# vidc_interposer2-PTH.net
KiCad netlist of a schematic drawn in EAGLE
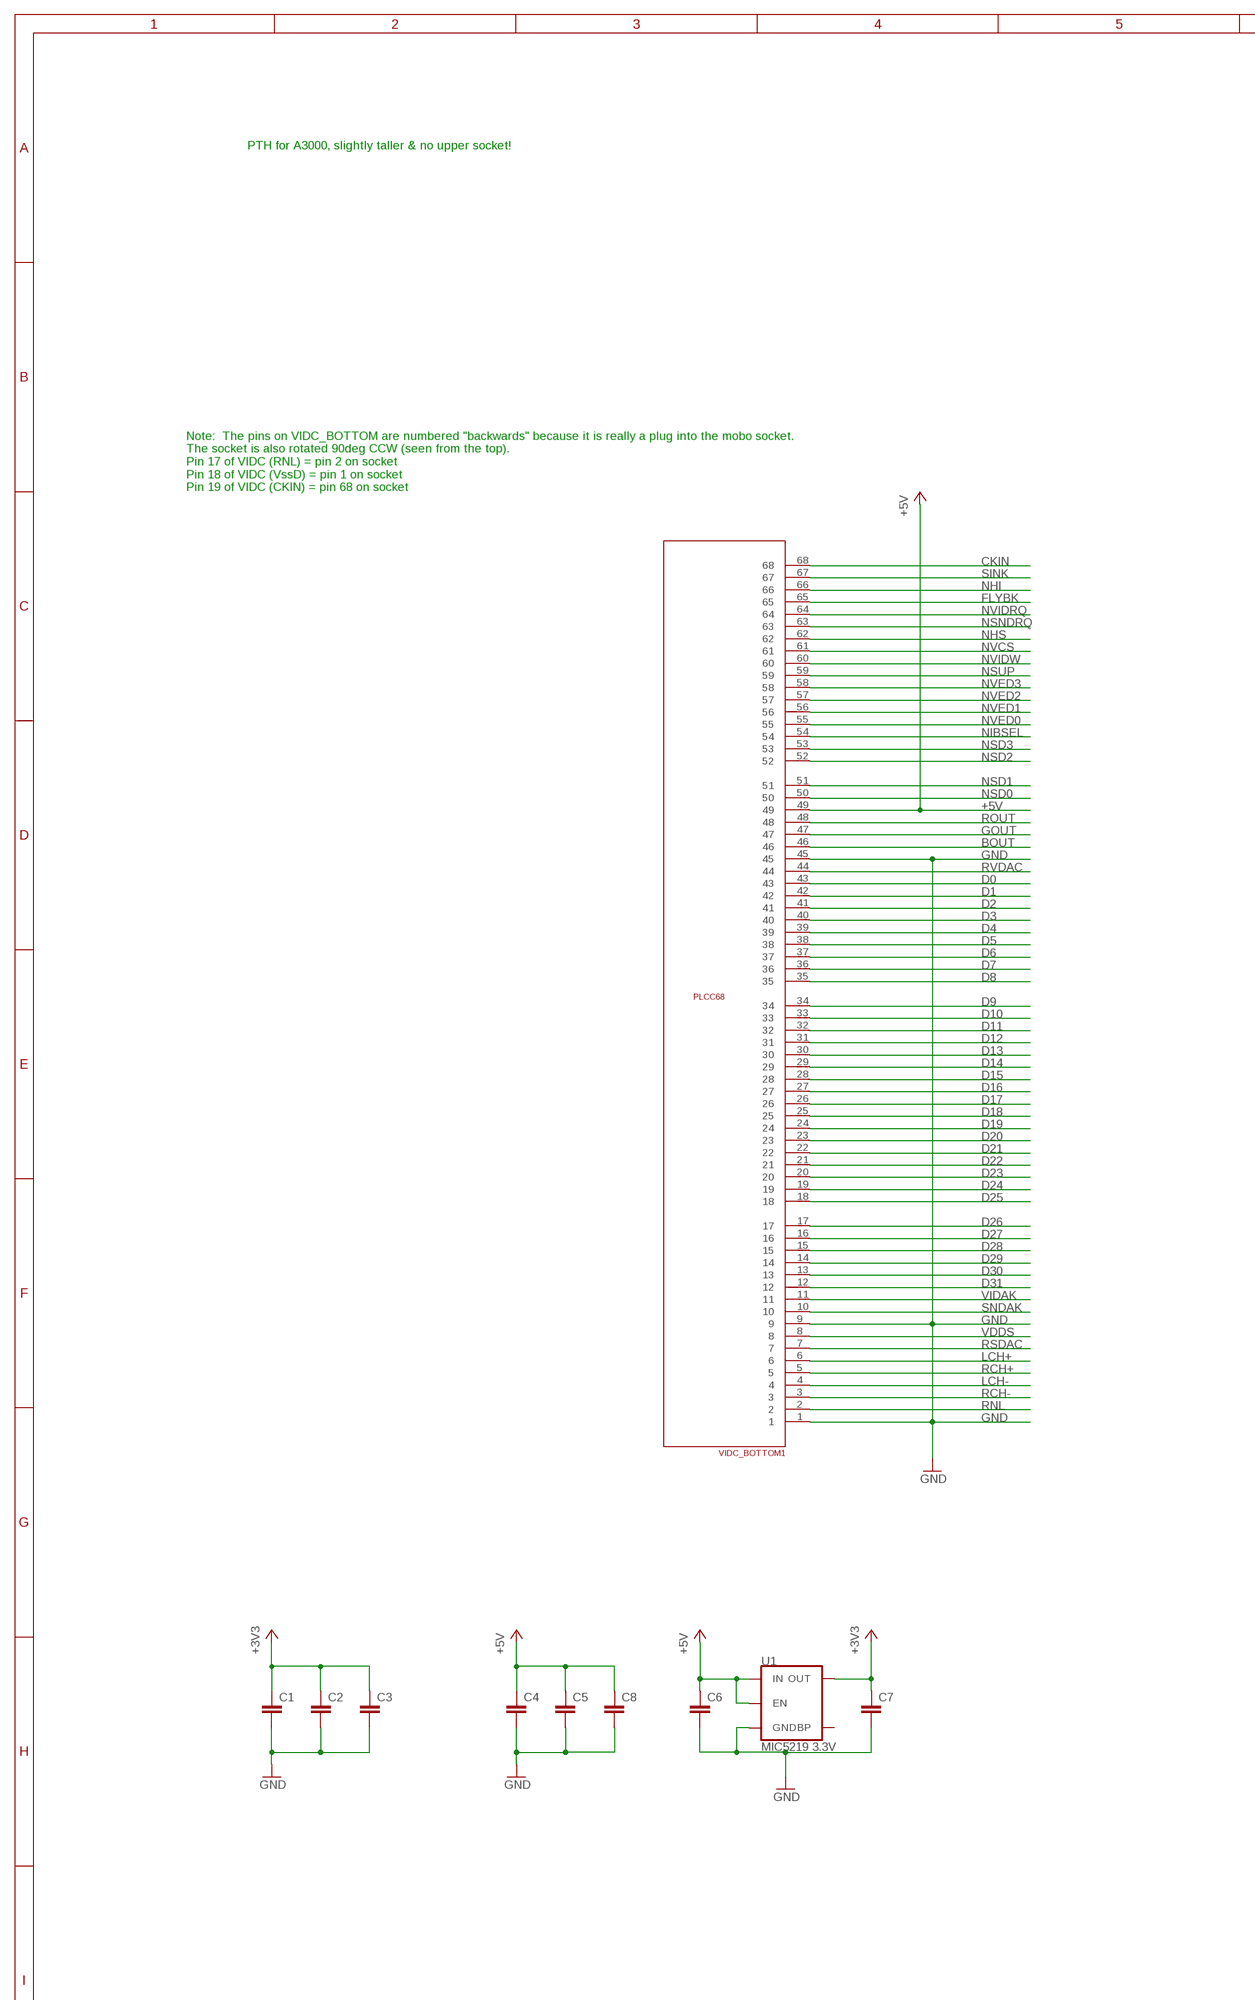
[diagram p0: schematic, sheet 1, part 1 of 2]
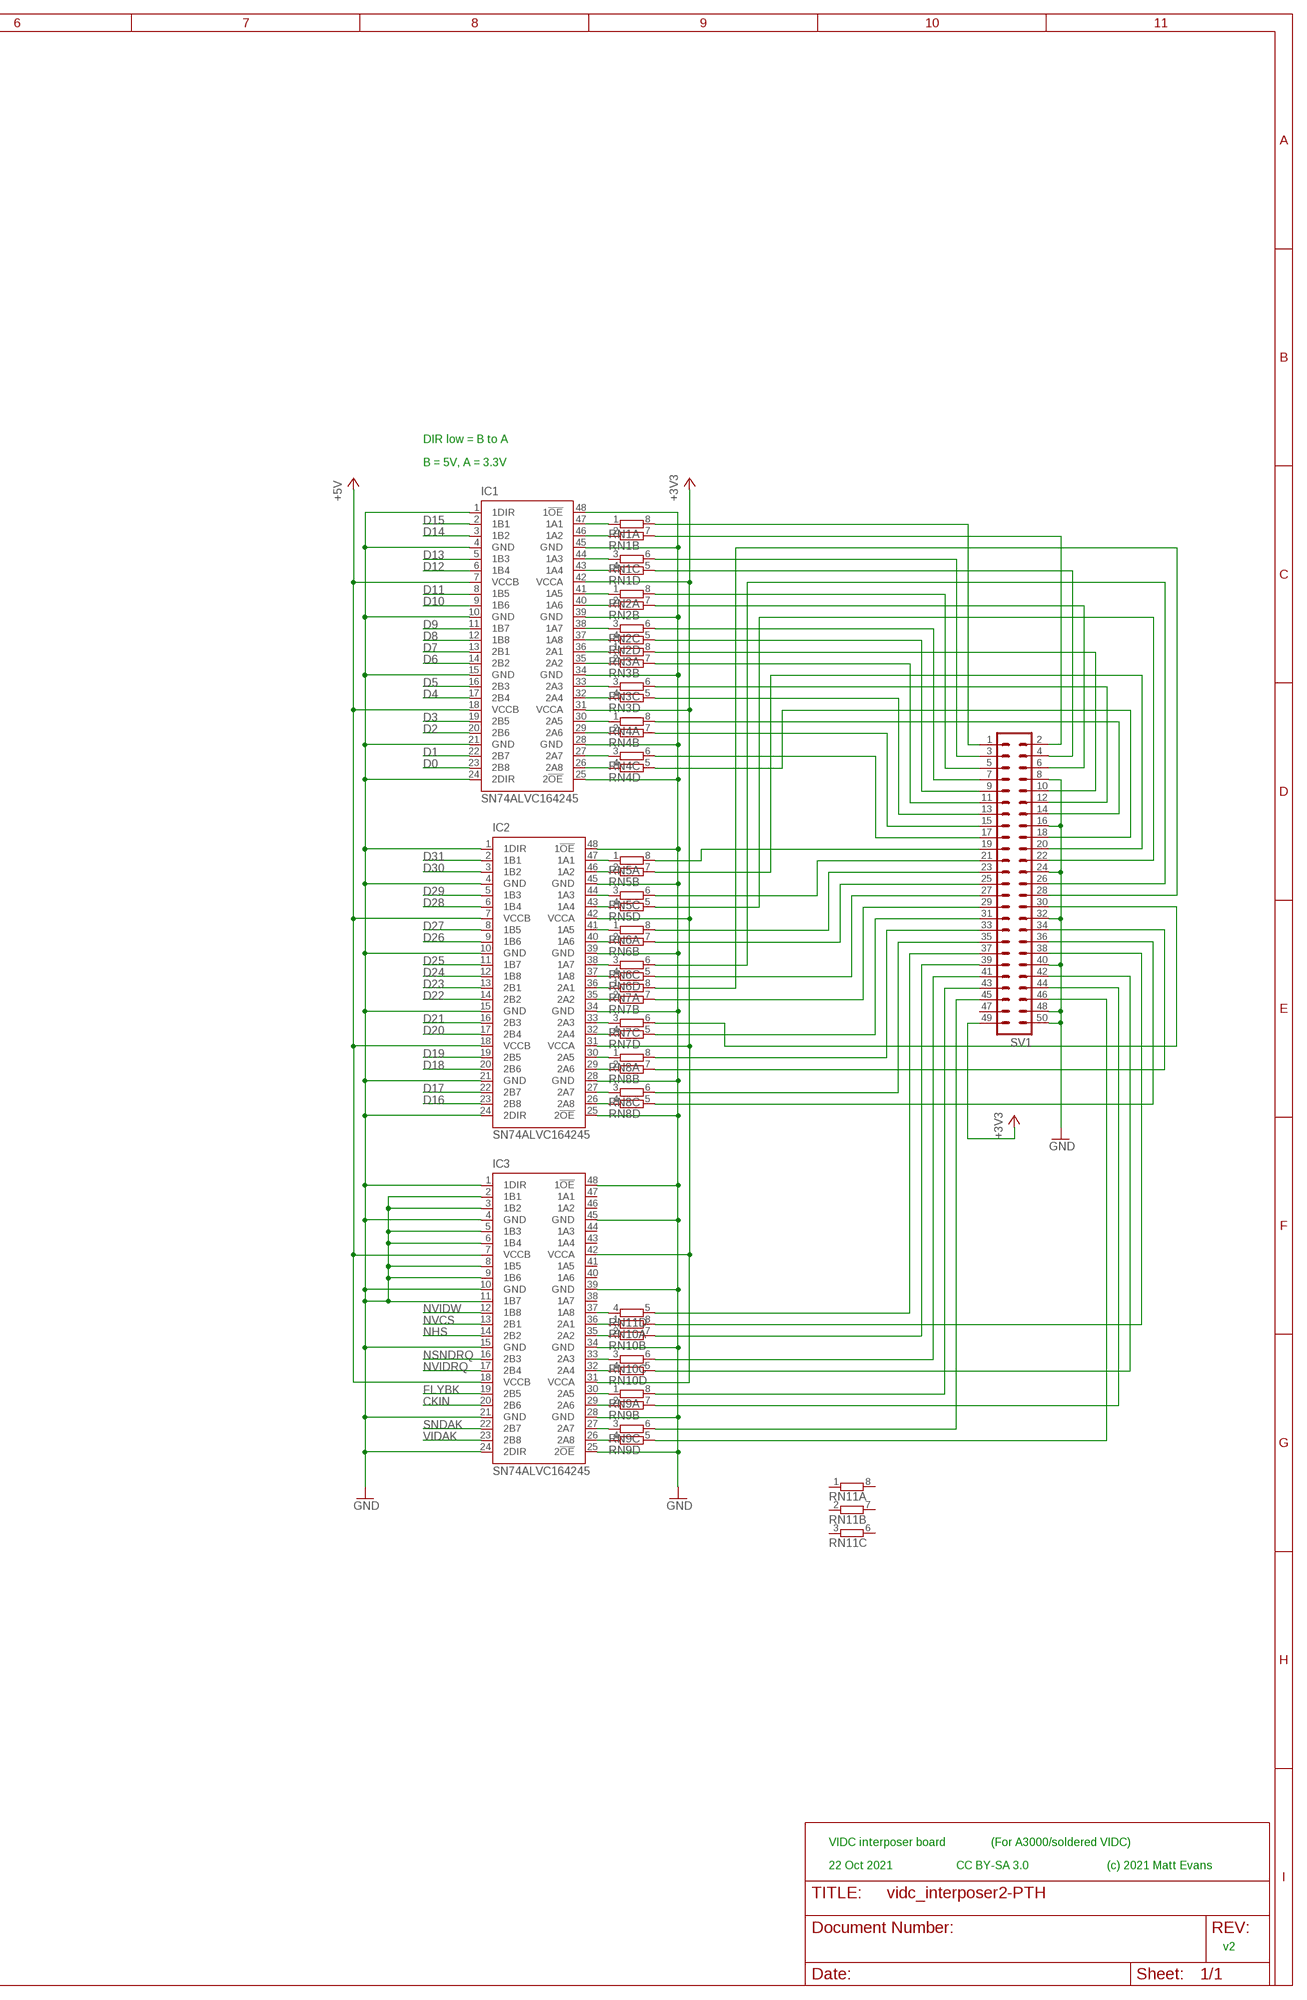
[diagram p1: schematic, sheet 1, part 2 of 2]

(export (version "E")
  (design (tool "Eeschema 10.0.6"))
  (components
    (comp (ref "C1")
      (value "C-EUC0805")
      (footprint "eagle-import:C0805")
      (libsource (lib "eagle-import") (part "C-EUC0805"))
    )
    (comp (ref "C2")
      (value "C-EUC0805")
      (footprint "eagle-import:C0805")
      (libsource (lib "eagle-import") (part "C-EUC0805"))
    )
    (comp (ref "C3")
      (value "C-EUC0805")
      (footprint "eagle-import:C0805")
      (libsource (lib "eagle-import") (part "C-EUC0805"))
    )
    (comp (ref "C4")
      (value "C-EUC0805")
      (footprint "eagle-import:C0805")
      (libsource (lib "eagle-import") (part "C-EUC0805"))
    )
    (comp (ref "C5")
      (value "C-EUC0805")
      (footprint "eagle-import:C0805")
      (libsource (lib "eagle-import") (part "C-EUC0805"))
    )
    (comp (ref "C6")
      (value "C-EUC0805")
      (footprint "eagle-import:C0805")
      (libsource (lib "eagle-import") (part "C-EUC0805"))
    )
    (comp (ref "C7")
      (value "C-EUC0805")
      (footprint "eagle-import:C0805")
      (libsource (lib "eagle-import") (part "C-EUC0805"))
    )
    (comp (ref "C8")
      (value "C-EUC0805")
      (footprint "eagle-import:C0805")
      (libsource (lib "eagle-import") (part "C-EUC0805"))
    )
    (comp (ref "IC1")
      (value "SN74ALVC164245")
      (footprint "eagle-import:DL_R-PDSO-G48")
      (fields (field (name "MPN") "SN74LVCR162245DL"))
      (libsource (lib "eagle-import") (part "SN74ALVC164245"))
    )
    (comp (ref "IC2")
      (value "SN74ALVC164245")
      (footprint "eagle-import:DL_R-PDSO-G48")
      (fields (field (name "MPN") "SN74LVCR162245DL"))
      (libsource (lib "eagle-import") (part "SN74ALVC164245"))
    )
    (comp (ref "IC3")
      (value "SN74ALVC164245")
      (footprint "eagle-import:DL_R-PDSO-G48")
      (fields (field (name "MPN") "SN74LVCR162245DL"))
      (libsource (lib "eagle-import") (part "SN74ALVC164245"))
    )
    (comp (ref "RN1")
      (value "4R-NCAY16")
      (footprint "eagle-import:CAY16")
      (libsource (lib "eagle-import") (part "4R-NCAY16"))
    )
    (comp (ref "RN2")
      (value "4R-NCAY16")
      (footprint "eagle-import:CAY16")
      (libsource (lib "eagle-import") (part "4R-NCAY16"))
    )
    (comp (ref "RN3")
      (value "4R-NCAY16")
      (footprint "eagle-import:CAY16")
      (libsource (lib "eagle-import") (part "4R-NCAY16"))
    )
    (comp (ref "RN4")
      (value "4R-NCAY16")
      (footprint "eagle-import:CAY16")
      (libsource (lib "eagle-import") (part "4R-NCAY16"))
    )
    (comp (ref "RN5")
      (value "4R-NCAY16")
      (footprint "eagle-import:CAY16")
      (libsource (lib "eagle-import") (part "4R-NCAY16"))
    )
    (comp (ref "RN6")
      (value "4R-NCAY16")
      (footprint "eagle-import:CAY16")
      (libsource (lib "eagle-import") (part "4R-NCAY16"))
    )
    (comp (ref "RN7")
      (value "4R-NCAY16")
      (footprint "eagle-import:CAY16")
      (libsource (lib "eagle-import") (part "4R-NCAY16"))
    )
    (comp (ref "RN8")
      (value "4R-NCAY16")
      (footprint "eagle-import:CAY16")
      (libsource (lib "eagle-import") (part "4R-NCAY16"))
    )
    (comp (ref "RN9")
      (value "4R-NCAY16")
      (footprint "eagle-import:CAY16")
      (libsource (lib "eagle-import") (part "4R-NCAY16"))
    )
    (comp (ref "RN10")
      (value "4R-NCAY16")
      (footprint "eagle-import:CAY16")
      (libsource (lib "eagle-import") (part "4R-NCAY16"))
    )
    (comp (ref "RN11")
      (value "4R-NCAY16")
      (footprint "eagle-import:CAY16")
      (libsource (lib "eagle-import") (part "4R-NCAY16"))
    )
    (comp (ref "SV1")
      (value "ML50")
      (footprint "eagle-import:ML50")
      (libsource (lib "eagle-import") (part "ML50"))
    )
    (comp (ref "U1")
      (value "MIC5219 3.3V")
      (footprint "eagle-import:SOT23-5")
      (libsource (lib "eagle-import") (part "V_REG_MIC52193.3V"))
    )
    (comp (ref "VIDC_BOTTOM1")
      (value "RAW_PLCC68PTH")
      (footprint "eagle-import:S68")
      (libsource (lib "eagle-import") (part "RAW_PLCC68PTH"))
    )
  )
  (nets
    (net (code "1") (name "+3V3") (class "Default")
      (node (ref "C1") (pin "1") (pinfunction "1_1") (pintype "passive"))
      (node (ref "C2") (pin "1") (pinfunction "1_1") (pintype "passive"))
      (node (ref "C3") (pin "1") (pinfunction "1_1") (pintype "passive"))
      (node (ref "C7") (pin "1") (pinfunction "1_1") (pintype "passive"))
      (node (ref "IC1") (pin "31") (pinfunction "VCCA_31") (pintype "power_in"))
      (node (ref "IC1") (pin "42") (pinfunction "VCCA_42") (pintype "power_in"))
      (node (ref "IC2") (pin "31") (pinfunction "VCCA_31") (pintype "power_in"))
      (node (ref "IC2") (pin "42") (pinfunction "VCCA_42") (pintype "power_in"))
      (node (ref "IC3") (pin "31") (pinfunction "VCCA_31") (pintype "power_in"))
      (node (ref "IC3") (pin "42") (pinfunction "VCCA_42") (pintype "power_in"))
      (node (ref "SV1") (pin "49") (pinfunction "49_49") (pintype "passive"))
      (node (ref "U1") (pin "5") (pinfunction "OUT_5") (pintype "passive"))
    )
    (net (code "2") (name "+5V") (class "Default")
      (node (ref "C4") (pin "1") (pinfunction "1_1") (pintype "passive"))
      (node (ref "C5") (pin "1") (pinfunction "1_1") (pintype "passive"))
      (node (ref "C6") (pin "1") (pinfunction "1_1") (pintype "passive"))
      (node (ref "C8") (pin "1") (pinfunction "1_1") (pintype "passive"))
      (node (ref "IC1") (pin "18") (pinfunction "VCCB_18") (pintype "power_in"))
      (node (ref "IC1") (pin "7") (pinfunction "VCCB_7") (pintype "power_in"))
      (node (ref "IC2") (pin "18") (pinfunction "VCCB_18") (pintype "power_in"))
      (node (ref "IC2") (pin "7") (pinfunction "VCCB_7") (pintype "power_in"))
      (node (ref "IC3") (pin "18") (pinfunction "VCCB_18") (pintype "power_in"))
      (node (ref "IC3") (pin "7") (pinfunction "VCCB_7") (pintype "power_in"))
      (node (ref "U1") (pin "1") (pinfunction "IN_1") (pintype "input"))
      (node (ref "U1") (pin "3") (pinfunction "EN_3") (pintype "input"))
      (node (ref "VIDC_BOTTOM1") (pin "49") (pinfunction "49_49") (pintype "bidirectional"))
    )
    (net (code "3") (name "/BOUT") (class "Default")
      (node (ref "VIDC_BOTTOM1") (pin "46") (pinfunction "46_46") (pintype "bidirectional"))
    )
    (net (code "4") (name "/CKIN") (class "Default")
      (node (ref "IC3") (pin "20") (pinfunction "2B6_20") (pintype "tri_state"))
      (node (ref "VIDC_BOTTOM1") (pin "68") (pinfunction "68_68") (pintype "bidirectional"))
    )
    (net (code "5") (name "/D0") (class "Default")
      (node (ref "IC1") (pin "23") (pinfunction "2B8_23") (pintype "tri_state"))
      (node (ref "VIDC_BOTTOM1") (pin "43") (pinfunction "43_43") (pintype "bidirectional"))
    )
    (net (code "6") (name "/D1") (class "Default")
      (node (ref "IC1") (pin "22") (pinfunction "2B7_22") (pintype "tri_state"))
      (node (ref "VIDC_BOTTOM1") (pin "42") (pinfunction "42_42") (pintype "bidirectional"))
    )
    (net (code "7") (name "/D2") (class "Default")
      (node (ref "IC1") (pin "20") (pinfunction "2B6_20") (pintype "tri_state"))
      (node (ref "VIDC_BOTTOM1") (pin "41") (pinfunction "41_41") (pintype "bidirectional"))
    )
    (net (code "8") (name "/D3") (class "Default")
      (node (ref "IC1") (pin "19") (pinfunction "2B5_19") (pintype "tri_state"))
      (node (ref "VIDC_BOTTOM1") (pin "40") (pinfunction "40_40") (pintype "bidirectional"))
    )
    (net (code "9") (name "/D4") (class "Default")
      (node (ref "IC1") (pin "17") (pinfunction "2B4_17") (pintype "tri_state"))
      (node (ref "VIDC_BOTTOM1") (pin "39") (pinfunction "39_39") (pintype "bidirectional"))
    )
    (net (code "10") (name "/D5") (class "Default")
      (node (ref "IC1") (pin "16") (pinfunction "2B3_16") (pintype "tri_state"))
      (node (ref "VIDC_BOTTOM1") (pin "38") (pinfunction "38_38") (pintype "bidirectional"))
    )
    (net (code "11") (name "/D6") (class "Default")
      (node (ref "IC1") (pin "14") (pinfunction "2B2_14") (pintype "tri_state"))
      (node (ref "VIDC_BOTTOM1") (pin "37") (pinfunction "37_37") (pintype "bidirectional"))
    )
    (net (code "12") (name "/D7") (class "Default")
      (node (ref "IC1") (pin "13") (pinfunction "2B1_13") (pintype "tri_state"))
      (node (ref "VIDC_BOTTOM1") (pin "36") (pinfunction "36_36") (pintype "bidirectional"))
    )
    (net (code "13") (name "/D8") (class "Default")
      (node (ref "IC1") (pin "12") (pinfunction "1B8_12") (pintype "tri_state"))
      (node (ref "VIDC_BOTTOM1") (pin "35") (pinfunction "35_35") (pintype "bidirectional"))
    )
    (net (code "14") (name "/D9") (class "Default")
      (node (ref "IC1") (pin "11") (pinfunction "1B7_11") (pintype "tri_state"))
      (node (ref "VIDC_BOTTOM1") (pin "34") (pinfunction "34_34") (pintype "bidirectional"))
    )
    (net (code "15") (name "/D10") (class "Default")
      (node (ref "IC1") (pin "9") (pinfunction "1B6_9") (pintype "tri_state"))
      (node (ref "VIDC_BOTTOM1") (pin "33") (pinfunction "33_33") (pintype "bidirectional"))
    )
    (net (code "16") (name "/D11") (class "Default")
      (node (ref "IC1") (pin "8") (pinfunction "1B5_8") (pintype "tri_state"))
      (node (ref "VIDC_BOTTOM1") (pin "32") (pinfunction "32_32") (pintype "bidirectional"))
    )
    (net (code "17") (name "/D12") (class "Default")
      (node (ref "IC1") (pin "6") (pinfunction "1B4_6") (pintype "tri_state"))
      (node (ref "VIDC_BOTTOM1") (pin "31") (pinfunction "31_31") (pintype "bidirectional"))
    )
    (net (code "18") (name "/D13") (class "Default")
      (node (ref "IC1") (pin "5") (pinfunction "1B3_5") (pintype "tri_state"))
      (node (ref "VIDC_BOTTOM1") (pin "30") (pinfunction "30_30") (pintype "bidirectional"))
    )
    (net (code "19") (name "/D14") (class "Default")
      (node (ref "IC1") (pin "3") (pinfunction "1B2_3") (pintype "tri_state"))
      (node (ref "VIDC_BOTTOM1") (pin "29") (pinfunction "29_29") (pintype "bidirectional"))
    )
    (net (code "20") (name "/D15") (class "Default")
      (node (ref "IC1") (pin "2") (pinfunction "1B1_2") (pintype "tri_state"))
      (node (ref "VIDC_BOTTOM1") (pin "28") (pinfunction "28_28") (pintype "bidirectional"))
    )
    (net (code "21") (name "/D16") (class "Default")
      (node (ref "IC2") (pin "23") (pinfunction "2B8_23") (pintype "tri_state"))
      (node (ref "VIDC_BOTTOM1") (pin "27") (pinfunction "27_27") (pintype "bidirectional"))
    )
    (net (code "22") (name "/D17") (class "Default")
      (node (ref "IC2") (pin "22") (pinfunction "2B7_22") (pintype "tri_state"))
      (node (ref "VIDC_BOTTOM1") (pin "26") (pinfunction "26_26") (pintype "bidirectional"))
    )
    (net (code "23") (name "/D18") (class "Default")
      (node (ref "IC2") (pin "20") (pinfunction "2B6_20") (pintype "tri_state"))
      (node (ref "VIDC_BOTTOM1") (pin "25") (pinfunction "25_25") (pintype "bidirectional"))
    )
    (net (code "24") (name "/D19") (class "Default")
      (node (ref "IC2") (pin "19") (pinfunction "2B5_19") (pintype "tri_state"))
      (node (ref "VIDC_BOTTOM1") (pin "24") (pinfunction "24_24") (pintype "bidirectional"))
    )
    (net (code "25") (name "/D20") (class "Default")
      (node (ref "IC2") (pin "17") (pinfunction "2B4_17") (pintype "tri_state"))
      (node (ref "VIDC_BOTTOM1") (pin "23") (pinfunction "23_23") (pintype "bidirectional"))
    )
    (net (code "26") (name "/D21") (class "Default")
      (node (ref "IC2") (pin "16") (pinfunction "2B3_16") (pintype "tri_state"))
      (node (ref "VIDC_BOTTOM1") (pin "22") (pinfunction "22_22") (pintype "bidirectional"))
    )
    (net (code "27") (name "/D22") (class "Default")
      (node (ref "IC2") (pin "14") (pinfunction "2B2_14") (pintype "tri_state"))
      (node (ref "VIDC_BOTTOM1") (pin "21") (pinfunction "21_21") (pintype "bidirectional"))
    )
    (net (code "28") (name "/D23") (class "Default")
      (node (ref "IC2") (pin "13") (pinfunction "2B1_13") (pintype "tri_state"))
      (node (ref "VIDC_BOTTOM1") (pin "20") (pinfunction "20_20") (pintype "bidirectional"))
    )
    (net (code "29") (name "/D24") (class "Default")
      (node (ref "IC2") (pin "12") (pinfunction "1B8_12") (pintype "tri_state"))
      (node (ref "VIDC_BOTTOM1") (pin "19") (pinfunction "19_19") (pintype "bidirectional"))
    )
    (net (code "30") (name "/D25") (class "Default")
      (node (ref "IC2") (pin "11") (pinfunction "1B7_11") (pintype "tri_state"))
      (node (ref "VIDC_BOTTOM1") (pin "18") (pinfunction "18_18") (pintype "bidirectional"))
    )
    (net (code "31") (name "/D26") (class "Default")
      (node (ref "IC2") (pin "9") (pinfunction "1B6_9") (pintype "tri_state"))
      (node (ref "VIDC_BOTTOM1") (pin "17") (pinfunction "17_17") (pintype "bidirectional"))
    )
    (net (code "32") (name "/D27") (class "Default")
      (node (ref "IC2") (pin "8") (pinfunction "1B5_8") (pintype "tri_state"))
      (node (ref "VIDC_BOTTOM1") (pin "16") (pinfunction "16_16") (pintype "bidirectional"))
    )
    (net (code "33") (name "/D28") (class "Default")
      (node (ref "IC2") (pin "6") (pinfunction "1B4_6") (pintype "tri_state"))
      (node (ref "VIDC_BOTTOM1") (pin "15") (pinfunction "15_15") (pintype "bidirectional"))
    )
    (net (code "34") (name "/D29") (class "Default")
      (node (ref "IC2") (pin "5") (pinfunction "1B3_5") (pintype "tri_state"))
      (node (ref "VIDC_BOTTOM1") (pin "14") (pinfunction "14_14") (pintype "bidirectional"))
    )
    (net (code "35") (name "/D30") (class "Default")
      (node (ref "IC2") (pin "3") (pinfunction "1B2_3") (pintype "tri_state"))
      (node (ref "VIDC_BOTTOM1") (pin "13") (pinfunction "13_13") (pintype "bidirectional"))
    )
    (net (code "36") (name "/D31") (class "Default")
      (node (ref "IC2") (pin "2") (pinfunction "1B1_2") (pintype "tri_state"))
      (node (ref "VIDC_BOTTOM1") (pin "12") (pinfunction "12_12") (pintype "bidirectional"))
    )
    (net (code "37") (name "/FLYBK") (class "Default")
      (node (ref "IC3") (pin "19") (pinfunction "2B5_19") (pintype "tri_state"))
      (node (ref "VIDC_BOTTOM1") (pin "65") (pinfunction "65_65") (pintype "bidirectional"))
    )
    (net (code "38") (name "/GOUT") (class "Default")
      (node (ref "VIDC_BOTTOM1") (pin "47") (pinfunction "47_47") (pintype "bidirectional"))
    )
    (net (code "39") (name "/LCH+") (class "Default")
      (node (ref "VIDC_BOTTOM1") (pin "6") (pinfunction "6_6") (pintype "bidirectional"))
    )
    (net (code "40") (name "/LCH-") (class "Default")
      (node (ref "VIDC_BOTTOM1") (pin "4") (pinfunction "4_4") (pintype "bidirectional"))
    )
    (net (code "41") (name "/NHI") (class "Default")
      (node (ref "VIDC_BOTTOM1") (pin "66") (pinfunction "66_66") (pintype "bidirectional"))
    )
    (net (code "42") (name "/NHS") (class "Default")
      (node (ref "IC3") (pin "14") (pinfunction "2B2_14") (pintype "tri_state"))
      (node (ref "VIDC_BOTTOM1") (pin "62") (pinfunction "62_62") (pintype "bidirectional"))
    )
    (net (code "43") (name "/NIBSEL") (class "Default")
      (node (ref "VIDC_BOTTOM1") (pin "54") (pinfunction "54_54") (pintype "bidirectional"))
    )
    (net (code "44") (name "/NSD0") (class "Default")
      (node (ref "VIDC_BOTTOM1") (pin "50") (pinfunction "50_50") (pintype "bidirectional"))
    )
    (net (code "45") (name "/NSD1") (class "Default")
      (node (ref "VIDC_BOTTOM1") (pin "51") (pinfunction "51_51") (pintype "bidirectional"))
    )
    (net (code "46") (name "/NSD2") (class "Default")
      (node (ref "VIDC_BOTTOM1") (pin "52") (pinfunction "52_52") (pintype "bidirectional"))
    )
    (net (code "47") (name "/NSD3") (class "Default")
      (node (ref "VIDC_BOTTOM1") (pin "53") (pinfunction "53_53") (pintype "bidirectional"))
    )
    (net (code "48") (name "/NSNDRQ") (class "Default")
      (node (ref "IC3") (pin "16") (pinfunction "2B3_16") (pintype "tri_state"))
      (node (ref "VIDC_BOTTOM1") (pin "63") (pinfunction "63_63") (pintype "bidirectional"))
    )
    (net (code "49") (name "/NSUP") (class "Default")
      (node (ref "VIDC_BOTTOM1") (pin "59") (pinfunction "59_59") (pintype "bidirectional"))
    )
    (net (code "50") (name "/NVCS") (class "Default")
      (node (ref "IC3") (pin "13") (pinfunction "2B1_13") (pintype "tri_state"))
      (node (ref "VIDC_BOTTOM1") (pin "61") (pinfunction "61_61") (pintype "bidirectional"))
    )
    (net (code "51") (name "/NVED0") (class "Default")
      (node (ref "VIDC_BOTTOM1") (pin "55") (pinfunction "55_55") (pintype "bidirectional"))
    )
    (net (code "52") (name "/NVED1") (class "Default")
      (node (ref "VIDC_BOTTOM1") (pin "56") (pinfunction "56_56") (pintype "bidirectional"))
    )
    (net (code "53") (name "/NVED2") (class "Default")
      (node (ref "VIDC_BOTTOM1") (pin "57") (pinfunction "57_57") (pintype "bidirectional"))
    )
    (net (code "54") (name "/NVED3") (class "Default")
      (node (ref "VIDC_BOTTOM1") (pin "58") (pinfunction "58_58") (pintype "bidirectional"))
    )
    (net (code "55") (name "/NVIDRQ") (class "Default")
      (node (ref "IC3") (pin "17") (pinfunction "2B4_17") (pintype "tri_state"))
      (node (ref "VIDC_BOTTOM1") (pin "64") (pinfunction "64_64") (pintype "bidirectional"))
    )
    (net (code "56") (name "/NVIDW") (class "Default")
      (node (ref "IC3") (pin "12") (pinfunction "1B8_12") (pintype "tri_state"))
      (node (ref "VIDC_BOTTOM1") (pin "60") (pinfunction "60_60") (pintype "bidirectional"))
    )
    (net (code "57") (name "/RCH+") (class "Default")
      (node (ref "VIDC_BOTTOM1") (pin "5") (pinfunction "5_5") (pintype "bidirectional"))
    )
    (net (code "58") (name "/RCH-") (class "Default")
      (node (ref "VIDC_BOTTOM1") (pin "3") (pinfunction "3_3") (pintype "bidirectional"))
    )
    (net (code "59") (name "/RNL") (class "Default")
      (node (ref "VIDC_BOTTOM1") (pin "2") (pinfunction "2_2") (pintype "bidirectional"))
    )
    (net (code "60") (name "/ROUT") (class "Default")
      (node (ref "VIDC_BOTTOM1") (pin "48") (pinfunction "48_48") (pintype "bidirectional"))
    )
    (net (code "61") (name "/RSDAC") (class "Default")
      (node (ref "VIDC_BOTTOM1") (pin "7") (pinfunction "7_7") (pintype "bidirectional"))
    )
    (net (code "62") (name "/RVDAC") (class "Default")
      (node (ref "VIDC_BOTTOM1") (pin "44") (pinfunction "44_44") (pintype "bidirectional"))
    )
    (net (code "63") (name "/SINK") (class "Default")
      (node (ref "VIDC_BOTTOM1") (pin "67") (pinfunction "67_67") (pintype "bidirectional"))
    )
    (net (code "64") (name "/SNDAK") (class "Default")
      (node (ref "IC3") (pin "22") (pinfunction "2B7_22") (pintype "tri_state"))
      (node (ref "VIDC_BOTTOM1") (pin "10") (pinfunction "10_10") (pintype "bidirectional"))
    )
    (net (code "65") (name "/VDDS") (class "Default")
      (node (ref "VIDC_BOTTOM1") (pin "8") (pinfunction "8_8") (pintype "bidirectional"))
    )
    (net (code "66") (name "/VIDAK") (class "Default")
      (node (ref "IC3") (pin "23") (pinfunction "2B8_23") (pintype "tri_state"))
      (node (ref "VIDC_BOTTOM1") (pin "11") (pinfunction "11_11") (pintype "bidirectional"))
    )
    (net (code "67") (name "GND") (class "Default")
      (node (ref "C1") (pin "2") (pinfunction "2_2") (pintype "passive"))
      (node (ref "C2") (pin "2") (pinfunction "2_2") (pintype "passive"))
      (node (ref "C3") (pin "2") (pinfunction "2_2") (pintype "passive"))
      (node (ref "C4") (pin "2") (pinfunction "2_2") (pintype "passive"))
      (node (ref "C5") (pin "2") (pinfunction "2_2") (pintype "passive"))
      (node (ref "C6") (pin "2") (pinfunction "2_2") (pintype "passive"))
      (node (ref "C7") (pin "2") (pinfunction "2_2") (pintype "passive"))
      (node (ref "C8") (pin "2") (pinfunction "2_2") (pintype "passive"))
      (node (ref "IC1") (pin "1") (pinfunction "1DIR_1") (pintype "input"))
      (node (ref "IC1") (pin "10") (pinfunction "GND_10") (pintype "power_in"))
      (node (ref "IC1") (pin "15") (pinfunction "GND_15") (pintype "power_in"))
      (node (ref "IC1") (pin "21") (pinfunction "GND_21") (pintype "tri_state"))
      (node (ref "IC1") (pin "24") (pinfunction "2DIR_24") (pintype "input"))
      (node (ref "IC1") (pin "25") (pinfunction "2~{OE}_25") (pintype "input"))
      (node (ref "IC1") (pin "28") (pinfunction "GND_28") (pintype "power_in"))
      (node (ref "IC1") (pin "34") (pinfunction "GND_34") (pintype "power_in"))
      (node (ref "IC1") (pin "39") (pinfunction "GND_39") (pintype "tri_state"))
      (node (ref "IC1") (pin "4") (pinfunction "GND_4") (pintype "power_in"))
      (node (ref "IC1") (pin "45") (pinfunction "GND_45") (pintype "power_in"))
      (node (ref "IC1") (pin "48") (pinfunction "1~{OE}_48") (pintype "input"))
      (node (ref "IC2") (pin "1") (pinfunction "1DIR_1") (pintype "input"))
      (node (ref "IC2") (pin "10") (pinfunction "GND_10") (pintype "power_in"))
      (node (ref "IC2") (pin "15") (pinfunction "GND_15") (pintype "power_in"))
      (node (ref "IC2") (pin "21") (pinfunction "GND_21") (pintype "tri_state"))
      (node (ref "IC2") (pin "24") (pinfunction "2DIR_24") (pintype "input"))
      (node (ref "IC2") (pin "25") (pinfunction "2~{OE}_25") (pintype "input"))
      (node (ref "IC2") (pin "28") (pinfunction "GND_28") (pintype "power_in"))
      (node (ref "IC2") (pin "34") (pinfunction "GND_34") (pintype "power_in"))
      (node (ref "IC2") (pin "39") (pinfunction "GND_39") (pintype "tri_state"))
      (node (ref "IC2") (pin "4") (pinfunction "GND_4") (pintype "power_in"))
      (node (ref "IC2") (pin "45") (pinfunction "GND_45") (pintype "power_in"))
      (node (ref "IC2") (pin "48") (pinfunction "1~{OE}_48") (pintype "input"))
      (node (ref "IC3") (pin "1") (pinfunction "1DIR_1") (pintype "input"))
      (node (ref "IC3") (pin "10") (pinfunction "GND_10") (pintype "power_in"))
      (node (ref "IC3") (pin "11") (pinfunction "1B7_11") (pintype "tri_state"))
      (node (ref "IC3") (pin "15") (pinfunction "GND_15") (pintype "power_in"))
      (node (ref "IC3") (pin "2") (pinfunction "1B1_2") (pintype "tri_state"))
      (node (ref "IC3") (pin "21") (pinfunction "GND_21") (pintype "tri_state"))
      (node (ref "IC3") (pin "24") (pinfunction "2DIR_24") (pintype "input"))
      (node (ref "IC3") (pin "25") (pinfunction "2~{OE}_25") (pintype "input"))
      (node (ref "IC3") (pin "28") (pinfunction "GND_28") (pintype "power_in"))
      (node (ref "IC3") (pin "3") (pinfunction "1B2_3") (pintype "tri_state"))
      (node (ref "IC3") (pin "34") (pinfunction "GND_34") (pintype "power_in"))
      (node (ref "IC3") (pin "39") (pinfunction "GND_39") (pintype "tri_state"))
      (node (ref "IC3") (pin "4") (pinfunction "GND_4") (pintype "power_in"))
      (node (ref "IC3") (pin "45") (pinfunction "GND_45") (pintype "power_in"))
      (node (ref "IC3") (pin "48") (pinfunction "1~{OE}_48") (pintype "input"))
      (node (ref "IC3") (pin "5") (pinfunction "1B3_5") (pintype "tri_state"))
      (node (ref "IC3") (pin "6") (pinfunction "1B4_6") (pintype "tri_state"))
      (node (ref "IC3") (pin "8") (pinfunction "1B5_8") (pintype "tri_state"))
      (node (ref "IC3") (pin "9") (pinfunction "1B6_9") (pintype "tri_state"))
      (node (ref "SV1") (pin "16") (pinfunction "16_16") (pintype "passive"))
      (node (ref "SV1") (pin "24") (pinfunction "24_24") (pintype "passive"))
      (node (ref "SV1") (pin "32") (pinfunction "32_32") (pintype "passive"))
      (node (ref "SV1") (pin "40") (pinfunction "40_40") (pintype "passive"))
      (node (ref "SV1") (pin "48") (pinfunction "48_48") (pintype "passive"))
      (node (ref "SV1") (pin "50") (pinfunction "50_50") (pintype "passive"))
      (node (ref "SV1") (pin "8") (pinfunction "8_8") (pintype "passive"))
      (node (ref "U1") (pin "2") (pinfunction "GND_2") (pintype "input"))
      (node (ref "VIDC_BOTTOM1") (pin "1") (pinfunction "1_1") (pintype "bidirectional"))
      (node (ref "VIDC_BOTTOM1") (pin "45") (pinfunction "45_45") (pintype "bidirectional"))
      (node (ref "VIDC_BOTTOM1") (pin "9") (pinfunction "9_9") (pintype "bidirectional"))
    )
    (net (code "68") (name "Net-(IC1-1A1)") (class "Default")
      (node (ref "IC1") (pin "47") (pinfunction "1A1_47") (pintype "tri_state"))
      (node (ref "RN1") (pin "1") (pinfunction "1_1") (pintype "passive"))
    )
    (net (code "69") (name "Net-(IC1-1A2)") (class "Default")
      (node (ref "IC1") (pin "46") (pinfunction "1A2_46") (pintype "tri_state"))
      (node (ref "RN1") (pin "2") (pinfunction "1_2") (pintype "passive"))
    )
    (net (code "70") (name "Net-(IC1-1A3)") (class "Default")
      (node (ref "IC1") (pin "44") (pinfunction "1A3_44") (pintype "tri_state"))
      (node (ref "RN1") (pin "3") (pinfunction "1_3") (pintype "passive"))
    )
    (net (code "71") (name "Net-(IC1-1A4)") (class "Default")
      (node (ref "IC1") (pin "43") (pinfunction "1A4_43") (pintype "tri_state"))
      (node (ref "RN1") (pin "4") (pinfunction "1_4") (pintype "passive"))
    )
    (net (code "72") (name "Net-(IC1-1A5)") (class "Default")
      (node (ref "IC1") (pin "41") (pinfunction "1A5_41") (pintype "tri_state"))
      (node (ref "RN2") (pin "1") (pinfunction "1_1") (pintype "passive"))
    )
    (net (code "73") (name "Net-(IC1-1A6)") (class "Default")
      (node (ref "IC1") (pin "40") (pinfunction "1A6_40") (pintype "tri_state"))
      (node (ref "RN2") (pin "2") (pinfunction "1_2") (pintype "passive"))
    )
    (net (code "74") (name "Net-(IC1-1A7)") (class "Default")
      (node (ref "IC1") (pin "38") (pinfunction "1A7_38") (pintype "tri_state"))
      (node (ref "RN2") (pin "3") (pinfunction "1_3") (pintype "passive"))
    )
    (net (code "75") (name "Net-(IC1-1A8)") (class "Default")
      (node (ref "IC1") (pin "37") (pinfunction "1A8_37") (pintype "tri_state"))
      (node (ref "RN2") (pin "4") (pinfunction "1_4") (pintype "passive"))
    )
    (net (code "76") (name "Net-(IC1-2A1)") (class "Default")
      (node (ref "IC1") (pin "36") (pinfunction "2A1_36") (pintype "tri_state"))
      (node (ref "RN3") (pin "1") (pinfunction "1_1") (pintype "passive"))
    )
    (net (code "77") (name "Net-(IC1-2A2)") (class "Default")
      (node (ref "IC1") (pin "35") (pinfunction "2A2_35") (pintype "tri_state"))
      (node (ref "RN3") (pin "2") (pinfunction "1_2") (pintype "passive"))
    )
    (net (code "78") (name "Net-(IC1-2A3)") (class "Default")
      (node (ref "IC1") (pin "33") (pinfunction "2A3_33") (pintype "tri_state"))
      (node (ref "RN3") (pin "3") (pinfunction "1_3") (pintype "passive"))
    )
    (net (code "79") (name "Net-(IC1-2A4)") (class "Default")
      (node (ref "IC1") (pin "32") (pinfunction "2A4_32") (pintype "tri_state"))
      (node (ref "RN3") (pin "4") (pinfunction "1_4") (pintype "passive"))
    )
    (net (code "80") (name "Net-(IC1-2A5)") (class "Default")
      (node (ref "IC1") (pin "30") (pinfunction "2A5_30") (pintype "tri_state"))
      (node (ref "RN4") (pin "1") (pinfunction "1_1") (pintype "passive"))
    )
    (net (code "81") (name "Net-(IC1-2A6)") (class "Default")
      (node (ref "IC1") (pin "29") (pinfunction "2A6_29") (pintype "tri_state"))
      (node (ref "RN4") (pin "2") (pinfunction "1_2") (pintype "passive"))
    )
    (net (code "82") (name "Net-(IC1-2A7)") (class "Default")
      (node (ref "IC1") (pin "27") (pinfunction "2A7_27") (pintype "tri_state"))
      (node (ref "RN4") (pin "3") (pinfunction "1_3") (pintype "passive"))
    )
    (net (code "83") (name "Net-(IC1-2A8)") (class "Default")
      (node (ref "IC1") (pin "26") (pinfunction "2A8_26") (pintype "tri_state"))
      (node (ref "RN4") (pin "4") (pinfunction "1_4") (pintype "passive"))
    )
    (net (code "84") (name "Net-(IC2-1A1)") (class "Default")
      (node (ref "IC2") (pin "47") (pinfunction "1A1_47") (pintype "tri_state"))
      (node (ref "RN5") (pin "1") (pinfunction "1_1") (pintype "passive"))
    )
    (net (code "85") (name "Net-(IC2-1A2)") (class "Default")
      (node (ref "IC2") (pin "46") (pinfunction "1A2_46") (pintype "tri_state"))
      (node (ref "RN5") (pin "2") (pinfunction "1_2") (pintype "passive"))
    )
    (net (code "86") (name "Net-(IC2-1A3)") (class "Default")
      (node (ref "IC2") (pin "44") (pinfunction "1A3_44") (pintype "tri_state"))
      (node (ref "RN5") (pin "3") (pinfunction "1_3") (pintype "passive"))
    )
    (net (code "87") (name "Net-(IC2-1A4)") (class "Default")
      (node (ref "IC2") (pin "43") (pinfunction "1A4_43") (pintype "tri_state"))
      (node (ref "RN5") (pin "4") (pinfunction "1_4") (pintype "passive"))
    )
    (net (code "88") (name "Net-(IC2-1A5)") (class "Default")
      (node (ref "IC2") (pin "41") (pinfunction "1A5_41") (pintype "tri_state"))
      (node (ref "RN6") (pin "1") (pinfunction "1_1") (pintype "passive"))
    )
    (net (code "89") (name "Net-(IC2-1A6)") (class "Default")
      (node (ref "IC2") (pin "40") (pinfunction "1A6_40") (pintype "tri_state"))
      (node (ref "RN6") (pin "2") (pinfunction "1_2") (pintype "passive"))
    )
    (net (code "90") (name "Net-(IC2-1A7)") (class "Default")
      (node (ref "IC2") (pin "38") (pinfunction "1A7_38") (pintype "tri_state"))
      (node (ref "RN6") (pin "3") (pinfunction "1_3") (pintype "passive"))
    )
    (net (code "91") (name "Net-(IC2-1A8)") (class "Default")
      (node (ref "IC2") (pin "37") (pinfunction "1A8_37") (pintype "tri_state"))
      (node (ref "RN6") (pin "4") (pinfunction "1_4") (pintype "passive"))
    )
    (net (code "92") (name "Net-(IC2-2A1)") (class "Default")
      (node (ref "IC2") (pin "36") (pinfunction "2A1_36") (pintype "tri_state"))
      (node (ref "RN7") (pin "1") (pinfunction "1_1") (pintype "passive"))
    )
    (net (code "93") (name "Net-(IC2-2A2)") (class "Default")
      (node (ref "IC2") (pin "35") (pinfunction "2A2_35") (pintype "tri_state"))
      (node (ref "RN7") (pin "2") (pinfunction "1_2") (pintype "passive"))
    )
    (net (code "94") (name "Net-(IC2-2A3)") (class "Default")
      (node (ref "IC2") (pin "33") (pinfunction "2A3_33") (pintype "tri_state"))
      (node (ref "RN7") (pin "3") (pinfunction "1_3") (pintype "passive"))
    )
    (net (code "95") (name "Net-(IC2-2A4)") (class "Default")
      (node (ref "IC2") (pin "32") (pinfunction "2A4_32") (pintype "tri_state"))
      (node (ref "RN7") (pin "4") (pinfunction "1_4") (pintype "passive"))
    )
    (net (code "96") (name "Net-(IC2-2A5)") (class "Default")
      (node (ref "IC2") (pin "30") (pinfunction "2A5_30") (pintype "tri_state"))
      (node (ref "RN8") (pin "1") (pinfunction "1_1") (pintype "passive"))
    )
    (net (code "97") (name "Net-(IC2-2A6)") (class "Default")
      (node (ref "IC2") (pin "29") (pinfunction "2A6_29") (pintype "tri_state"))
      (node (ref "RN8") (pin "2") (pinfunction "1_2") (pintype "passive"))
    )
    (net (code "98") (name "Net-(IC2-2A7)") (class "Default")
      (node (ref "IC2") (pin "27") (pinfunction "2A7_27") (pintype "tri_state"))
      (node (ref "RN8") (pin "3") (pinfunction "1_3") (pintype "passive"))
    )
    (net (code "99") (name "Net-(IC2-2A8)") (class "Default")
      (node (ref "IC2") (pin "26") (pinfunction "2A8_26") (pintype "tri_state"))
      (node (ref "RN8") (pin "4") (pinfunction "1_4") (pintype "passive"))
    )
    (net (code "100") (name "Net-(IC3-1A8)") (class "Default")
      (node (ref "IC3") (pin "37") (pinfunction "1A8_37") (pintype "tri_state"))
      (node (ref "RN11") (pin "4") (pinfunction "1_4") (pintype "passive"))
    )
    (net (code "101") (name "Net-(IC3-2A1)") (class "Default")
      (node (ref "IC3") (pin "36") (pinfunction "2A1_36") (pintype "tri_state"))
      (node (ref "RN10") (pin "1") (pinfunction "1_1") (pintype "passive"))
    )
    (net (code "102") (name "Net-(IC3-2A2)") (class "Default")
      (node (ref "IC3") (pin "35") (pinfunction "2A2_35") (pintype "tri_state"))
      (node (ref "RN10") (pin "2") (pinfunction "1_2") (pintype "passive"))
    )
    (net (code "103") (name "Net-(IC3-2A3)") (class "Default")
      (node (ref "IC3") (pin "33") (pinfunction "2A3_33") (pintype "tri_state"))
      (node (ref "RN10") (pin "3") (pinfunction "1_3") (pintype "passive"))
    )
    (net (code "104") (name "Net-(IC3-2A4)") (class "Default")
      (node (ref "IC3") (pin "32") (pinfunction "2A4_32") (pintype "tri_state"))
      (node (ref "RN10") (pin "4") (pinfunction "1_4") (pintype "passive"))
    )
    (net (code "105") (name "Net-(IC3-2A5)") (class "Default")
      (node (ref "IC3") (pin "30") (pinfunction "2A5_30") (pintype "tri_state"))
      (node (ref "RN9") (pin "1") (pinfunction "1_1") (pintype "passive"))
    )
    (net (code "106") (name "Net-(IC3-2A6)") (class "Default")
      (node (ref "IC3") (pin "29") (pinfunction "2A6_29") (pintype "tri_state"))
      (node (ref "RN9") (pin "2") (pinfunction "1_2") (pintype "passive"))
    )
    (net (code "107") (name "Net-(IC3-2A7)") (class "Default")
      (node (ref "IC3") (pin "27") (pinfunction "2A7_27") (pintype "tri_state"))
      (node (ref "RN9") (pin "3") (pinfunction "1_3") (pintype "passive"))
    )
    (net (code "108") (name "Net-(IC3-2A8)") (class "Default")
      (node (ref "IC3") (pin "26") (pinfunction "2A8_26") (pintype "tri_state"))
      (node (ref "RN9") (pin "4") (pinfunction "1_4") (pintype "passive"))
    )
    (net (code "109") (name "Net-(RN1A-2)") (class "Default")
      (node (ref "RN1") (pin "8") (pinfunction "2_8") (pintype "passive"))
      (node (ref "SV1") (pin "1") (pinfunction "1_1") (pintype "passive"))
    )
    (net (code "110") (name "Net-(RN1B-2)") (class "Default")
      (node (ref "RN1") (pin "7") (pinfunction "2_7") (pintype "passive"))
      (node (ref "SV1") (pin "2") (pinfunction "2_2") (pintype "passive"))
    )
    (net (code "111") (name "Net-(RN1C-2)") (class "Default")
      (node (ref "RN1") (pin "6") (pinfunction "2_6") (pintype "passive"))
      (node (ref "SV1") (pin "3") (pinfunction "3_3") (pintype "passive"))
    )
    (net (code "112") (name "Net-(RN1D-2)") (class "Default")
      (node (ref "RN1") (pin "5") (pinfunction "2_5") (pintype "passive"))
      (node (ref "SV1") (pin "4") (pinfunction "4_4") (pintype "passive"))
    )
    (net (code "113") (name "Net-(RN2A-2)") (class "Default")
      (node (ref "RN2") (pin "8") (pinfunction "2_8") (pintype "passive"))
      (node (ref "SV1") (pin "5") (pinfunction "5_5") (pintype "passive"))
    )
    (net (code "114") (name "Net-(RN2B-2)") (class "Default")
      (node (ref "RN2") (pin "7") (pinfunction "2_7") (pintype "passive"))
      (node (ref "SV1") (pin "6") (pinfunction "6_6") (pintype "passive"))
    )
    (net (code "115") (name "Net-(RN2C-2)") (class "Default")
      (node (ref "RN2") (pin "6") (pinfunction "2_6") (pintype "passive"))
      (node (ref "SV1") (pin "7") (pinfunction "7_7") (pintype "passive"))
    )
    (net (code "116") (name "Net-(RN2D-2)") (class "Default")
      (node (ref "RN2") (pin "5") (pinfunction "2_5") (pintype "passive"))
      (node (ref "SV1") (pin "9") (pinfunction "9_9") (pintype "passive"))
    )
    (net (code "117") (name "Net-(RN3A-2)") (class "Default")
      (node (ref "RN3") (pin "8") (pinfunction "2_8") (pintype "passive"))
      (node (ref "SV1") (pin "10") (pinfunction "10_10") (pintype "passive"))
    )
    (net (code "118") (name "Net-(RN3B-2)") (class "Default")
      (node (ref "RN3") (pin "7") (pinfunction "2_7") (pintype "passive"))
      (node (ref "SV1") (pin "11") (pinfunction "11_11") (pintype "passive"))
    )
    (net (code "119") (name "Net-(RN3C-2)") (class "Default")
      (node (ref "RN3") (pin "6") (pinfunction "2_6") (pintype "passive"))
      (node (ref "SV1") (pin "12") (pinfunction "12_12") (pintype "passive"))
    )
    (net (code "120") (name "Net-(RN3D-2)") (class "Default")
      (node (ref "RN3") (pin "5") (pinfunction "2_5") (pintype "passive"))
      (node (ref "SV1") (pin "13") (pinfunction "13_13") (pintype "passive"))
    )
    (net (code "121") (name "Net-(RN4A-2)") (class "Default")
      (node (ref "RN4") (pin "8") (pinfunction "2_8") (pintype "passive"))
      (node (ref "SV1") (pin "14") (pinfunction "14_14") (pintype "passive"))
    )
    (net (code "122") (name "Net-(RN4B-2)") (class "Default")
      (node (ref "RN4") (pin "7") (pinfunction "2_7") (pintype "passive"))
      (node (ref "SV1") (pin "15") (pinfunction "15_15") (pintype "passive"))
    )
    (net (code "123") (name "Net-(RN4C-2)") (class "Default")
      (node (ref "RN4") (pin "6") (pinfunction "2_6") (pintype "passive"))
      (node (ref "SV1") (pin "17") (pinfunction "17_17") (pintype "passive"))
    )
    (net (code "124") (name "Net-(RN4D-2)") (class "Default")
      (node (ref "RN4") (pin "5") (pinfunction "2_5") (pintype "passive"))
      (node (ref "SV1") (pin "18") (pinfunction "18_18") (pintype "passive"))
    )
    (net (code "125") (name "Net-(RN5A-2)") (class "Default")
      (node (ref "RN5") (pin "8") (pinfunction "2_8") (pintype "passive"))
      (node (ref "SV1") (pin "19") (pinfunction "19_19") (pintype "passive"))
    )
    (net (code "126") (name "Net-(RN5B-2)") (class "Default")
      (node (ref "RN5") (pin "7") (pinfunction "2_7") (pintype "passive"))
      (node (ref "SV1") (pin "20") (pinfunction "20_20") (pintype "passive"))
    )
    (net (code "127") (name "Net-(RN5C-2)") (class "Default")
      (node (ref "RN5") (pin "6") (pinfunction "2_6") (pintype "passive"))
      (node (ref "SV1") (pin "21") (pinfunction "21_21") (pintype "passive"))
    )
    (net (code "128") (name "Net-(RN5D-2)") (class "Default")
      (node (ref "RN5") (pin "5") (pinfunction "2_5") (pintype "passive"))
      (node (ref "SV1") (pin "22") (pinfunction "22_22") (pintype "passive"))
    )
    (net (code "129") (name "Net-(RN6A-2)") (class "Default")
      (node (ref "RN6") (pin "8") (pinfunction "2_8") (pintype "passive"))
      (node (ref "SV1") (pin "23") (pinfunction "23_23") (pintype "passive"))
    )
    (net (code "130") (name "Net-(RN6B-2)") (class "Default")
      (node (ref "RN6") (pin "7") (pinfunction "2_7") (pintype "passive"))
      (node (ref "SV1") (pin "25") (pinfunction "25_25") (pintype "passive"))
    )
    (net (code "131") (name "Net-(RN6C-2)") (class "Default")
      (node (ref "RN6") (pin "6") (pinfunction "2_6") (pintype "passive"))
      (node (ref "SV1") (pin "26") (pinfunction "26_26") (pintype "passive"))
    )
    (net (code "132") (name "Net-(RN6D-2)") (class "Default")
      (node (ref "RN6") (pin "5") (pinfunction "2_5") (pintype "passive"))
      (node (ref "SV1") (pin "27") (pinfunction "27_27") (pintype "passive"))
    )
    (net (code "133") (name "Net-(RN7A-2)") (class "Default")
      (node (ref "RN7") (pin "8") (pinfunction "2_8") (pintype "passive"))
      (node (ref "SV1") (pin "28") (pinfunction "28_28") (pintype "passive"))
    )
    (net (code "134") (name "Net-(RN7B-2)") (class "Default")
      (node (ref "RN7") (pin "7") (pinfunction "2_7") (pintype "passive"))
      (node (ref "SV1") (pin "29") (pinfunction "29_29") (pintype "passive"))
    )
    (net (code "135") (name "Net-(RN7C-2)") (class "Default")
      (node (ref "RN7") (pin "6") (pinfunction "2_6") (pintype "passive"))
      (node (ref "SV1") (pin "30") (pinfunction "30_30") (pintype "passive"))
    )
    (net (code "136") (name "Net-(RN7D-2)") (class "Default")
      (node (ref "RN7") (pin "5") (pinfunction "2_5") (pintype "passive"))
      (node (ref "SV1") (pin "31") (pinfunction "31_31") (pintype "passive"))
    )
    (net (code "137") (name "Net-(RN8A-2)") (class "Default")
      (node (ref "RN8") (pin "8") (pinfunction "2_8") (pintype "passive"))
      (node (ref "SV1") (pin "33") (pinfunction "33_33") (pintype "passive"))
    )
    (net (code "138") (name "Net-(RN8B-2)") (class "Default")
      (node (ref "RN8") (pin "7") (pinfunction "2_7") (pintype "passive"))
      (node (ref "SV1") (pin "34") (pinfunction "34_34") (pintype "passive"))
    )
    (net (code "139") (name "Net-(RN8C-2)") (class "Default")
      (node (ref "RN8") (pin "6") (pinfunction "2_6") (pintype "passive"))
      (node (ref "SV1") (pin "35") (pinfunction "35_35") (pintype "passive"))
    )
    (net (code "140") (name "Net-(RN8D-2)") (class "Default")
      (node (ref "RN8") (pin "5") (pinfunction "2_5") (pintype "passive"))
      (node (ref "SV1") (pin "36") (pinfunction "36_36") (pintype "passive"))
    )
    (net (code "141") (name "Net-(RN9A-2)") (class "Default")
      (node (ref "RN9") (pin "8") (pinfunction "2_8") (pintype "passive"))
      (node (ref "SV1") (pin "43") (pinfunction "43_43") (pintype "passive"))
    )
    (net (code "142") (name "Net-(RN9B-2)") (class "Default")
      (node (ref "RN9") (pin "7") (pinfunction "2_7") (pintype "passive"))
      (node (ref "SV1") (pin "44") (pinfunction "44_44") (pintype "passive"))
    )
    (net (code "143") (name "Net-(RN9C-2)") (class "Default")
      (node (ref "RN9") (pin "6") (pinfunction "2_6") (pintype "passive"))
      (node (ref "SV1") (pin "45") (pinfunction "45_45") (pintype "passive"))
    )
    (net (code "144") (name "Net-(RN9D-2)") (class "Default")
      (node (ref "RN9") (pin "5") (pinfunction "2_5") (pintype "passive"))
      (node (ref "SV1") (pin "46") (pinfunction "46_46") (pintype "passive"))
    )
    (net (code "145") (name "Net-(RN10A-2)") (class "Default")
      (node (ref "RN10") (pin "8") (pinfunction "2_8") (pintype "passive"))
      (node (ref "SV1") (pin "38") (pinfunction "38_38") (pintype "passive"))
    )
    (net (code "146") (name "Net-(RN10B-2)") (class "Default")
      (node (ref "RN10") (pin "7") (pinfunction "2_7") (pintype "passive"))
      (node (ref "SV1") (pin "39") (pinfunction "39_39") (pintype "passive"))
    )
    (net (code "147") (name "Net-(RN10C-2)") (class "Default")
      (node (ref "RN10") (pin "6") (pinfunction "2_6") (pintype "passive"))
      (node (ref "SV1") (pin "41") (pinfunction "41_41") (pintype "passive"))
    )
    (net (code "148") (name "Net-(RN10D-2)") (class "Default")
      (node (ref "RN10") (pin "5") (pinfunction "2_5") (pintype "passive"))
      (node (ref "SV1") (pin "42") (pinfunction "42_42") (pintype "passive"))
    )
    (net (code "149") (name "Net-(RN11D-2)") (class "Default")
      (node (ref "RN11") (pin "5") (pinfunction "2_5") (pintype "passive"))
      (node (ref "SV1") (pin "37") (pinfunction "37_37") (pintype "passive"))
    )
    (net (code "150") (name "unconnected-(IC3-1A1-Pad47)") (class "Default")
      (node (ref "IC3") (pin "47") (pinfunction "1A1_47") (pintype "tri_state"))
    )
    (net (code "151") (name "unconnected-(IC3-1A2-Pad46)") (class "Default")
      (node (ref "IC3") (pin "46") (pinfunction "1A2_46") (pintype "tri_state"))
    )
    (net (code "152") (name "unconnected-(IC3-1A3-Pad44)") (class "Default")
      (node (ref "IC3") (pin "44") (pinfunction "1A3_44") (pintype "tri_state"))
    )
    (net (code "153") (name "unconnected-(IC3-1A4-Pad43)") (class "Default")
      (node (ref "IC3") (pin "43") (pinfunction "1A4_43") (pintype "tri_state"))
    )
    (net (code "154") (name "unconnected-(IC3-1A5-Pad41)") (class "Default")
      (node (ref "IC3") (pin "41") (pinfunction "1A5_41") (pintype "tri_state"))
    )
    (net (code "155") (name "unconnected-(IC3-1A6-Pad40)") (class "Default")
      (node (ref "IC3") (pin "40") (pinfunction "1A6_40") (pintype "tri_state"))
    )
    (net (code "156") (name "unconnected-(IC3-1A7-Pad38)") (class "Default")
      (node (ref "IC3") (pin "38") (pinfunction "1A7_38") (pintype "tri_state"))
    )
    (net (code "157") (name "unconnected-(RN11-Pad1)") (class "Default")
      (node (ref "RN11") (pin "1") (pinfunction "1_1") (pintype "passive"))
    )
    (net (code "158") (name "unconnected-(RN11A-2-Pad8)") (class "Default")
      (node (ref "RN11") (pin "8") (pinfunction "2_8") (pintype "passive"))
    )
    (net (code "159") (name "unconnected-(RN11B-1-Pad2)") (class "Default")
      (node (ref "RN11") (pin "2") (pinfunction "1_2") (pintype "passive"))
    )
    (net (code "160") (name "unconnected-(RN11B-2-Pad7)") (class "Default")
      (node (ref "RN11") (pin "7") (pinfunction "2_7") (pintype "passive"))
    )
    (net (code "161") (name "unconnected-(RN11C-1-Pad3)") (class "Default")
      (node (ref "RN11") (pin "3") (pinfunction "1_3") (pintype "passive"))
    )
    (net (code "162") (name "unconnected-(RN11C-2-Pad6)") (class "Default")
      (node (ref "RN11") (pin "6") (pinfunction "2_6") (pintype "passive"))
    )
    (net (code "163") (name "unconnected-(SV1-Pad47)") (class "Default")
      (node (ref "SV1") (pin "47") (pinfunction "47_47") (pintype "passive"))
    )
    (net (code "164") (name "unconnected-(U1-BP-Pad4)") (class "Default")
      (node (ref "U1") (pin "4") (pinfunction "BP_4") (pintype "input"))
    )
  )
)
